# led_3.net
KiCad netlist of a schematic drawn in EAGLE
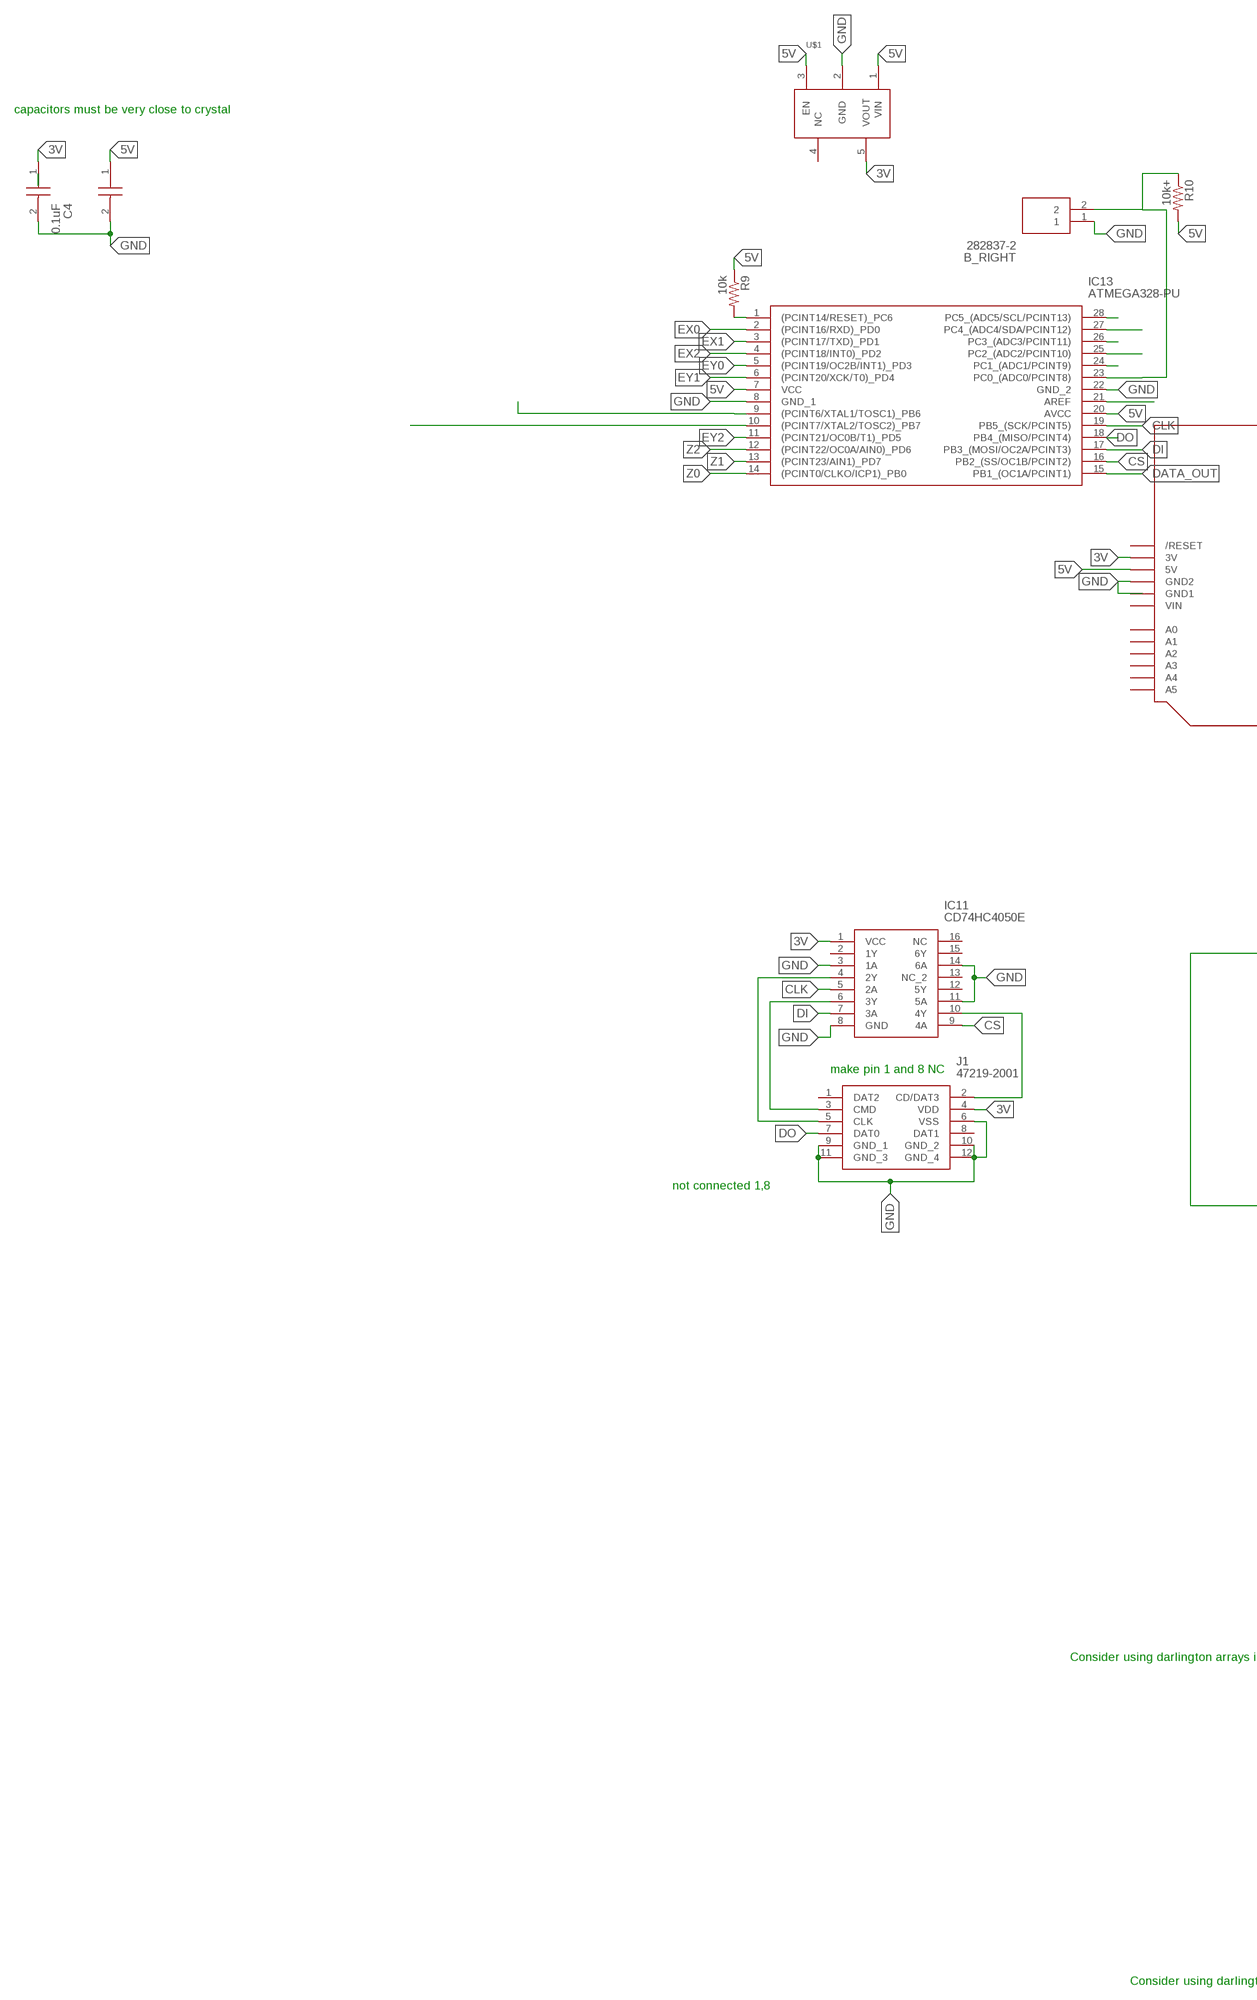
[diagram p0: schematic, sheet 1, part 1 of 2]
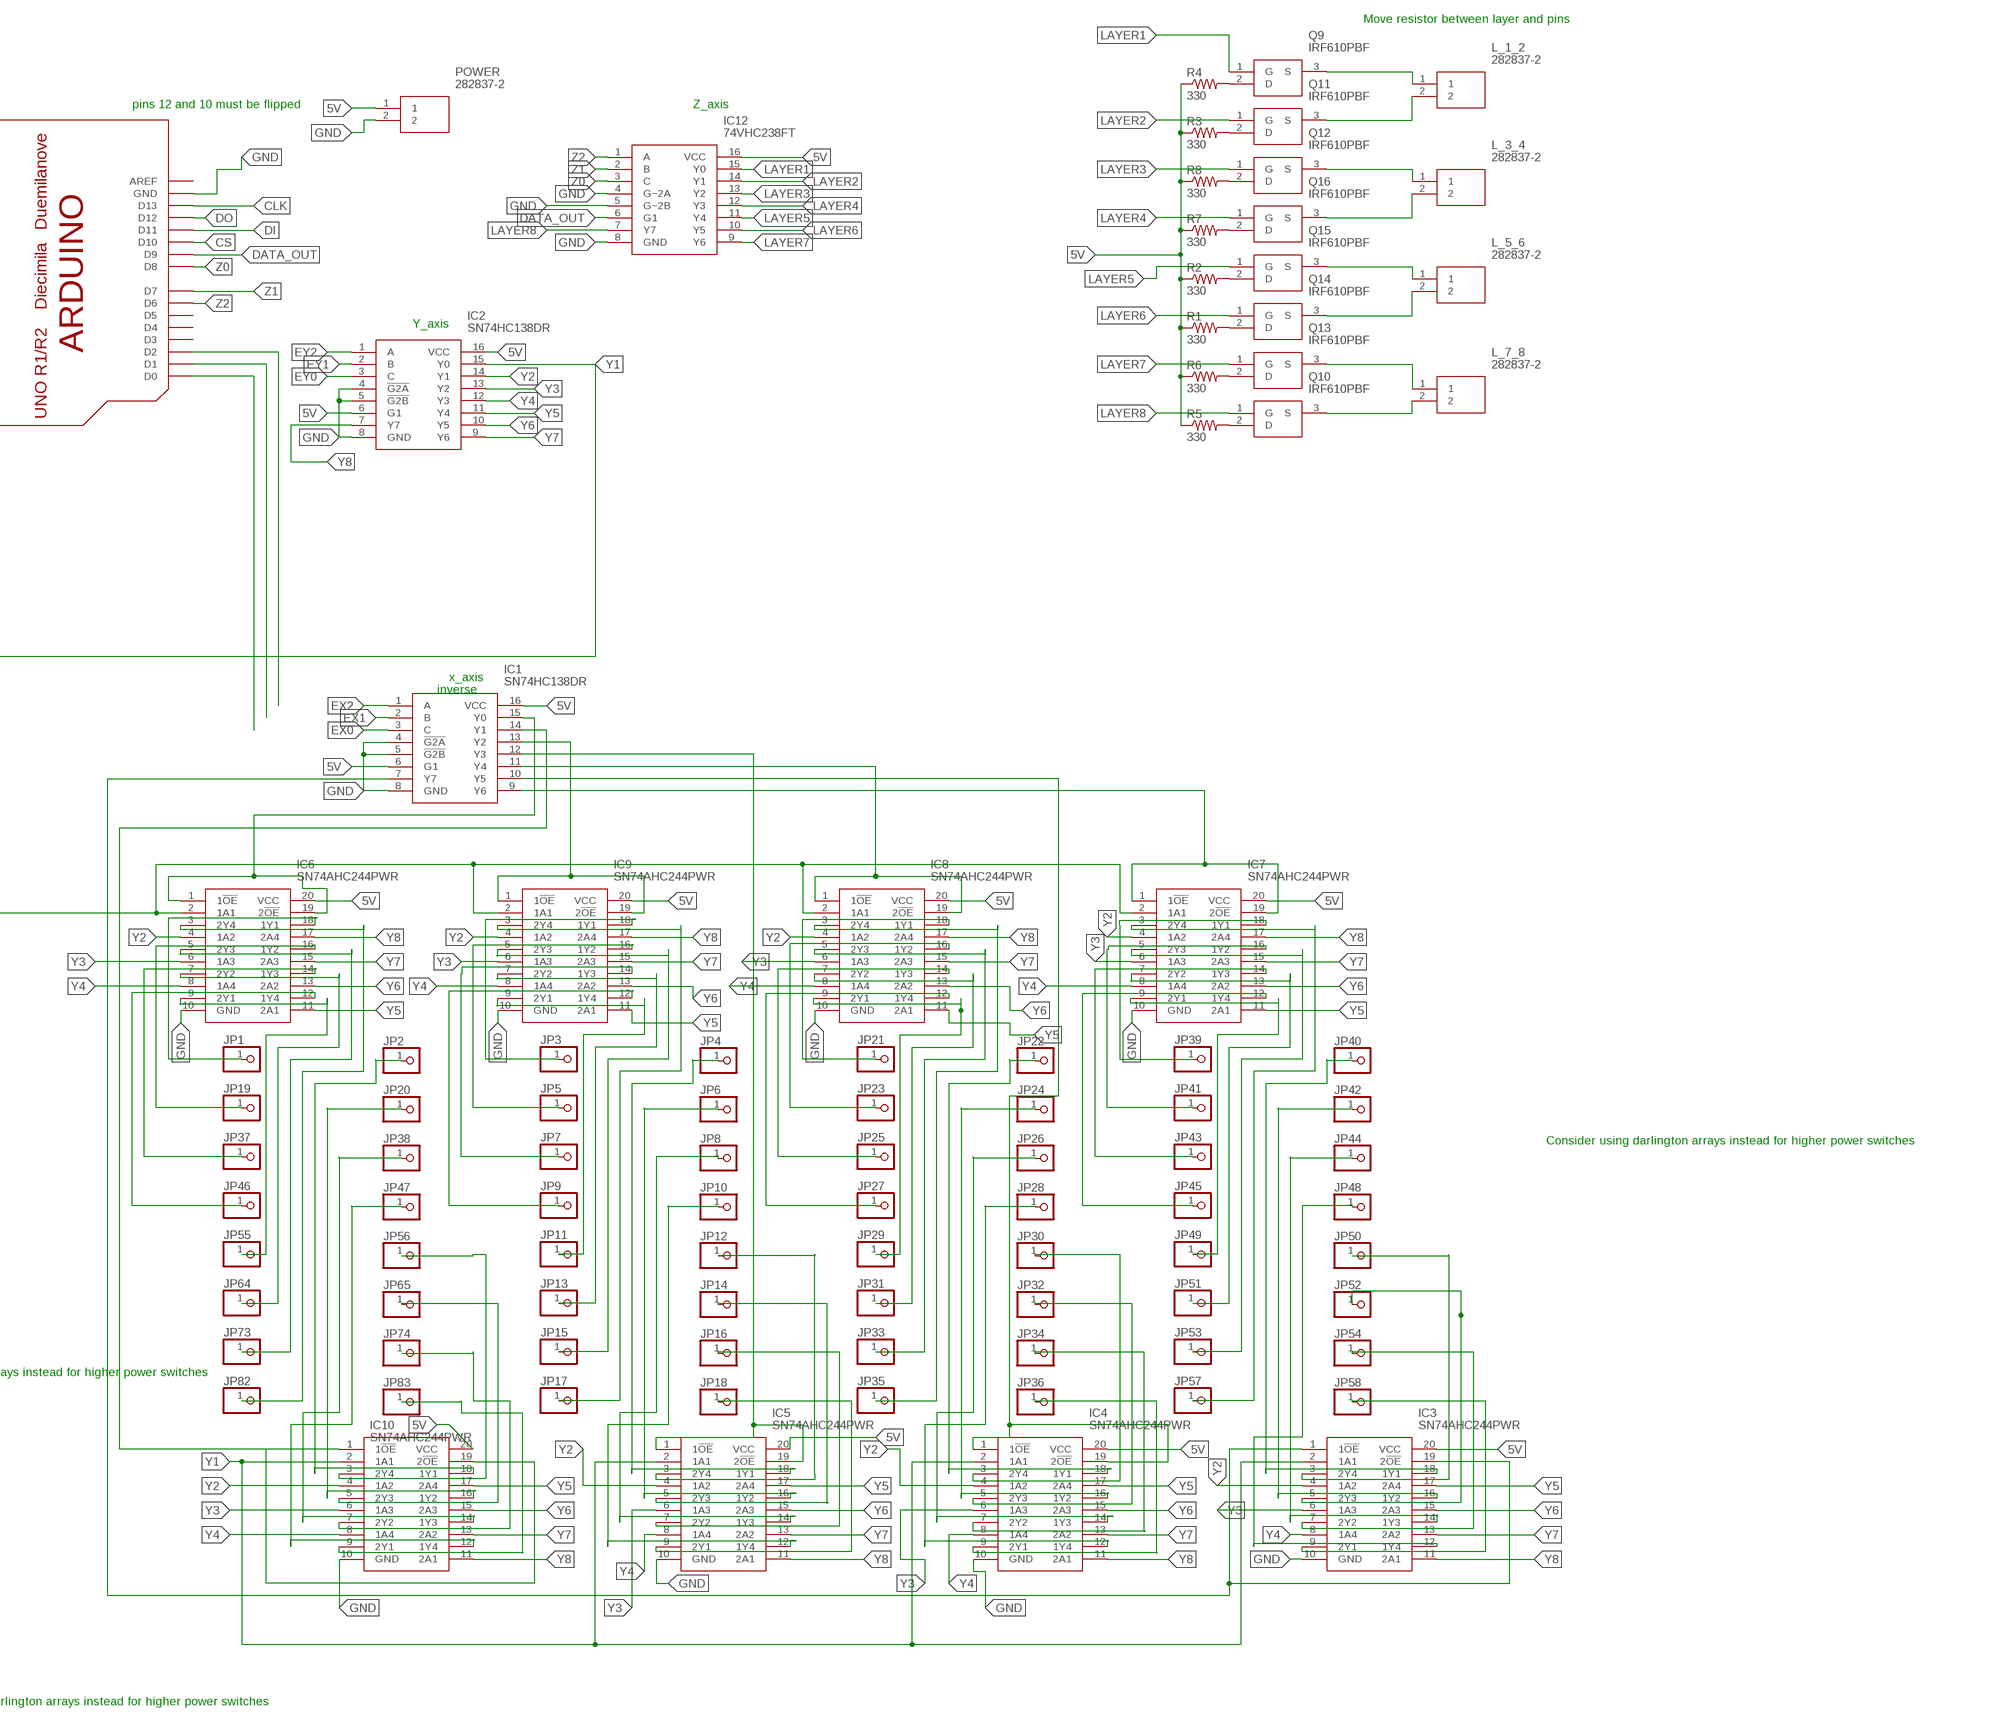
[diagram p1: schematic, sheet 1, part 2 of 2]

(export (version "E")
  (design (tool "Eeschema 10.0.6"))
  (components
    (comp (ref "B_RIGHT")
      (value "282837-2")
      (footprint "eagle-import:SHDR2W100P0X508_1X2_1016X820X1")
      (fields (field (name "MOUSER_PART_NUMBER") "571-2828372"))
      (libsource (lib "eagle-import") (part "282837-2"))
    )
    (comp (ref "C4")
      (value "0.1uF")
      (footprint "eagle-import:CAPC2012X88N")
      (fields
        (field (name "MANUFACTURER_PART_NUMBER") "C0805C224K3RACTU")
        (field (name "MOUSER_PART_NUMBER") "80-C0805C224K3R")
      )
      (libsource (lib "eagle-import") (part "C0805C224K3RACTU"))
    )
    (comp (ref "C5")
      (value "0.1uF")
      (footprint "eagle-import:CAPC2012X88N")
      (fields
        (field (name "MANUFACTURER_PART_NUMBER") "C0805C224K3RACTU")
        (field (name "MOUSER_PART_NUMBER") "80-C0805C224K3R")
      )
      (libsource (lib "eagle-import") (part "C0805C224K3RACTU"))
    )
    (comp (ref "IC1")
      (value "SN74HC138DR")
      (footprint "eagle-import:SOIC127P600X175-16N")
      (fields (field (name "MOUSER_PART_NUMBER") "595-SN74HC138DR"))
      (libsource (lib "eagle-import") (part "SN74HC138DR"))
    )
    (comp (ref "IC2")
      (value "SN74HC138DR")
      (footprint "eagle-import:SOIC127P600X175-16N")
      (fields (field (name "MOUSER_PART_NUMBER") "595-SN74HC138DR"))
      (libsource (lib "eagle-import") (part "SN74HC138DR"))
    )
    (comp (ref "IC3")
      (value "SN74AHC244PWR")
      (footprint "eagle-import:SOP65P640X120-20N")
      (fields (field (name "MOUSER_PART_NUMBER") "595-SN74AHC244PWR"))
      (libsource (lib "eagle-import") (part "SN74AHC244PWR"))
    )
    (comp (ref "IC4")
      (value "SN74AHC244PWR")
      (footprint "eagle-import:SOP65P640X120-20N")
      (fields (field (name "MOUSER_PART_NUMBER") "595-SN74AHC244PWR"))
      (libsource (lib "eagle-import") (part "SN74AHC244PWR"))
    )
    (comp (ref "IC5")
      (value "SN74AHC244PWR")
      (footprint "eagle-import:SOP65P640X120-20N")
      (fields (field (name "MOUSER_PART_NUMBER") "595-SN74AHC244PWR"))
      (libsource (lib "eagle-import") (part "SN74AHC244PWR"))
    )
    (comp (ref "IC6")
      (value "SN74AHC244PWR")
      (footprint "eagle-import:SOP65P640X120-20N")
      (fields (field (name "MOUSER_PART_NUMBER") "595-SN74AHC244PWR"))
      (libsource (lib "eagle-import") (part "SN74AHC244PWR"))
    )
    (comp (ref "IC7")
      (value "SN74AHC244PWR")
      (footprint "eagle-import:SOP65P640X120-20N")
      (fields (field (name "MOUSER_PART_NUMBER") "595-SN74AHC244PWR"))
      (libsource (lib "eagle-import") (part "SN74AHC244PWR"))
    )
    (comp (ref "IC8")
      (value "SN74AHC244PWR")
      (footprint "eagle-import:SOP65P640X120-20N")
      (fields (field (name "MOUSER_PART_NUMBER") "595-SN74AHC244PWR"))
      (libsource (lib "eagle-import") (part "SN74AHC244PWR"))
    )
    (comp (ref "IC9")
      (value "SN74AHC244PWR")
      (footprint "eagle-import:SOP65P640X120-20N")
      (fields (field (name "MOUSER_PART_NUMBER") "595-SN74AHC244PWR"))
      (libsource (lib "eagle-import") (part "SN74AHC244PWR"))
    )
    (comp (ref "IC10")
      (value "SN74AHC244PWR")
      (footprint "eagle-import:SOP65P640X120-20N")
      (fields (field (name "MOUSER_PART_NUMBER") "595-SN74AHC244PWR"))
      (libsource (lib "eagle-import") (part "SN74AHC244PWR"))
    )
    (comp (ref "IC11")
      (value "CD74HC4050E")
      (footprint "eagle-import:DIP254P762X508-16")
      (fields (field (name "MOUSER_PART_NUMBER") "595-CD74HC4050E"))
      (libsource (lib "eagle-import") (part "CD74HC4050E"))
    )
    (comp (ref "IC12")
      (value "74VHC238FT")
      (footprint "eagle-import:SOP65P640X120-16N")
      (libsource (lib "eagle-import") (part "74VHC238FT"))
    )
    (comp (ref "IC13")
      (value "ATMEGA328-PU")
      (footprint "eagle-import:DIP1016W53P254L3468H457Q28N")
      (fields (field (name "MOUSER_PART_NUMBER") "556-ATMEGA328-PU"))
      (libsource (lib "eagle-import") (part "ATMEGA328-PU"))
    )
    (comp (ref "J1")
      (value "47219-2001")
      (footprint "eagle-import:472192001")
      (fields (field (name "MOUSER_PART_NUMBER") "538-47219-2001"))
      (libsource (lib "eagle-import") (part "47219-2001"))
    )
    (comp (ref "JP1")
      (value "PINHD-1X1")
      (footprint "eagle-import:1X01")
      (libsource (lib "eagle-import") (part "PINHD-1X1"))
    )
    (comp (ref "JP2")
      (value "PINHD-1X1")
      (footprint "eagle-import:1X01")
      (libsource (lib "eagle-import") (part "PINHD-1X1"))
    )
    (comp (ref "JP3")
      (value "PINHD-1X1")
      (footprint "eagle-import:1X01")
      (libsource (lib "eagle-import") (part "PINHD-1X1"))
    )
    (comp (ref "JP4")
      (value "PINHD-1X1")
      (footprint "eagle-import:1X01")
      (libsource (lib "eagle-import") (part "PINHD-1X1"))
    )
    (comp (ref "JP5")
      (value "PINHD-1X1")
      (footprint "eagle-import:1X01")
      (libsource (lib "eagle-import") (part "PINHD-1X1"))
    )
    (comp (ref "JP6")
      (value "PINHD-1X1")
      (footprint "eagle-import:1X01")
      (libsource (lib "eagle-import") (part "PINHD-1X1"))
    )
    (comp (ref "JP7")
      (value "PINHD-1X1")
      (footprint "eagle-import:1X01")
      (libsource (lib "eagle-import") (part "PINHD-1X1"))
    )
    (comp (ref "JP8")
      (value "PINHD-1X1")
      (footprint "eagle-import:1X01")
      (libsource (lib "eagle-import") (part "PINHD-1X1"))
    )
    (comp (ref "JP9")
      (value "PINHD-1X1")
      (footprint "eagle-import:1X01")
      (libsource (lib "eagle-import") (part "PINHD-1X1"))
    )
    (comp (ref "JP10")
      (value "PINHD-1X1")
      (footprint "eagle-import:1X01")
      (libsource (lib "eagle-import") (part "PINHD-1X1"))
    )
    (comp (ref "JP11")
      (value "PINHD-1X1")
      (footprint "eagle-import:1X01")
      (libsource (lib "eagle-import") (part "PINHD-1X1"))
    )
    (comp (ref "JP12")
      (value "PINHD-1X1")
      (footprint "eagle-import:1X01")
      (libsource (lib "eagle-import") (part "PINHD-1X1"))
    )
    (comp (ref "JP13")
      (value "PINHD-1X1")
      (footprint "eagle-import:1X01")
      (libsource (lib "eagle-import") (part "PINHD-1X1"))
    )
    (comp (ref "JP14")
      (value "PINHD-1X1")
      (footprint "eagle-import:1X01")
      (libsource (lib "eagle-import") (part "PINHD-1X1"))
    )
    (comp (ref "JP15")
      (value "PINHD-1X1")
      (footprint "eagle-import:1X01")
      (libsource (lib "eagle-import") (part "PINHD-1X1"))
    )
    (comp (ref "JP16")
      (value "PINHD-1X1")
      (footprint "eagle-import:1X01")
      (libsource (lib "eagle-import") (part "PINHD-1X1"))
    )
    (comp (ref "JP17")
      (value "PINHD-1X1")
      (footprint "eagle-import:1X01")
      (libsource (lib "eagle-import") (part "PINHD-1X1"))
    )
    (comp (ref "JP18")
      (value "PINHD-1X1")
      (footprint "eagle-import:1X01")
      (libsource (lib "eagle-import") (part "PINHD-1X1"))
    )
    (comp (ref "JP19")
      (value "PINHD-1X1")
      (footprint "eagle-import:1X01")
      (libsource (lib "eagle-import") (part "PINHD-1X1"))
    )
    (comp (ref "JP20")
      (value "PINHD-1X1")
      (footprint "eagle-import:1X01")
      (libsource (lib "eagle-import") (part "PINHD-1X1"))
    )
    (comp (ref "JP21")
      (value "PINHD-1X1")
      (footprint "eagle-import:1X01")
      (libsource (lib "eagle-import") (part "PINHD-1X1"))
    )
    (comp (ref "JP22")
      (value "PINHD-1X1")
      (footprint "eagle-import:1X01")
      (libsource (lib "eagle-import") (part "PINHD-1X1"))
    )
    (comp (ref "JP23")
      (value "PINHD-1X1")
      (footprint "eagle-import:1X01")
      (libsource (lib "eagle-import") (part "PINHD-1X1"))
    )
    (comp (ref "JP24")
      (value "PINHD-1X1")
      (footprint "eagle-import:1X01")
      (libsource (lib "eagle-import") (part "PINHD-1X1"))
    )
    (comp (ref "JP25")
      (value "PINHD-1X1")
      (footprint "eagle-import:1X01")
      (libsource (lib "eagle-import") (part "PINHD-1X1"))
    )
    (comp (ref "JP26")
      (value "PINHD-1X1")
      (footprint "eagle-import:1X01")
      (libsource (lib "eagle-import") (part "PINHD-1X1"))
    )
    (comp (ref "JP27")
      (value "PINHD-1X1")
      (footprint "eagle-import:1X01")
      (libsource (lib "eagle-import") (part "PINHD-1X1"))
    )
    (comp (ref "JP28")
      (value "PINHD-1X1")
      (footprint "eagle-import:1X01")
      (libsource (lib "eagle-import") (part "PINHD-1X1"))
    )
    (comp (ref "JP29")
      (value "PINHD-1X1")
      (footprint "eagle-import:1X01")
      (libsource (lib "eagle-import") (part "PINHD-1X1"))
    )
    (comp (ref "JP30")
      (value "PINHD-1X1")
      (footprint "eagle-import:1X01")
      (libsource (lib "eagle-import") (part "PINHD-1X1"))
    )
    (comp (ref "JP31")
      (value "PINHD-1X1")
      (footprint "eagle-import:1X01")
      (libsource (lib "eagle-import") (part "PINHD-1X1"))
    )
    (comp (ref "JP32")
      (value "PINHD-1X1")
      (footprint "eagle-import:1X01")
      (libsource (lib "eagle-import") (part "PINHD-1X1"))
    )
    (comp (ref "JP33")
      (value "PINHD-1X1")
      (footprint "eagle-import:1X01")
      (libsource (lib "eagle-import") (part "PINHD-1X1"))
    )
    (comp (ref "JP34")
      (value "PINHD-1X1")
      (footprint "eagle-import:1X01")
      (libsource (lib "eagle-import") (part "PINHD-1X1"))
    )
    (comp (ref "JP35")
      (value "PINHD-1X1")
      (footprint "eagle-import:1X01")
      (libsource (lib "eagle-import") (part "PINHD-1X1"))
    )
    (comp (ref "JP36")
      (value "PINHD-1X1")
      (footprint "eagle-import:1X01")
      (libsource (lib "eagle-import") (part "PINHD-1X1"))
    )
    (comp (ref "JP37")
      (value "PINHD-1X1")
      (footprint "eagle-import:1X01")
      (libsource (lib "eagle-import") (part "PINHD-1X1"))
    )
    (comp (ref "JP38")
      (value "PINHD-1X1")
      (footprint "eagle-import:1X01")
      (libsource (lib "eagle-import") (part "PINHD-1X1"))
    )
    (comp (ref "JP39")
      (value "PINHD-1X1")
      (footprint "eagle-import:1X01")
      (libsource (lib "eagle-import") (part "PINHD-1X1"))
    )
    (comp (ref "JP40")
      (value "PINHD-1X1")
      (footprint "eagle-import:1X01")
      (libsource (lib "eagle-import") (part "PINHD-1X1"))
    )
    (comp (ref "JP41")
      (value "PINHD-1X1")
      (footprint "eagle-import:1X01")
      (libsource (lib "eagle-import") (part "PINHD-1X1"))
    )
    (comp (ref "JP42")
      (value "PINHD-1X1")
      (footprint "eagle-import:1X01")
      (libsource (lib "eagle-import") (part "PINHD-1X1"))
    )
    (comp (ref "JP43")
      (value "PINHD-1X1")
      (footprint "eagle-import:1X01")
      (libsource (lib "eagle-import") (part "PINHD-1X1"))
    )
    (comp (ref "JP44")
      (value "PINHD-1X1")
      (footprint "eagle-import:1X01")
      (libsource (lib "eagle-import") (part "PINHD-1X1"))
    )
    (comp (ref "JP45")
      (value "PINHD-1X1")
      (footprint "eagle-import:1X01")
      (libsource (lib "eagle-import") (part "PINHD-1X1"))
    )
    (comp (ref "JP46")
      (value "PINHD-1X1")
      (footprint "eagle-import:1X01")
      (libsource (lib "eagle-import") (part "PINHD-1X1"))
    )
    (comp (ref "JP47")
      (value "PINHD-1X1")
      (footprint "eagle-import:1X01")
      (libsource (lib "eagle-import") (part "PINHD-1X1"))
    )
    (comp (ref "JP48")
      (value "PINHD-1X1")
      (footprint "eagle-import:1X01")
      (libsource (lib "eagle-import") (part "PINHD-1X1"))
    )
    (comp (ref "JP49")
      (value "PINHD-1X1")
      (footprint "eagle-import:1X01")
      (libsource (lib "eagle-import") (part "PINHD-1X1"))
    )
    (comp (ref "JP50")
      (value "PINHD-1X1")
      (footprint "eagle-import:1X01")
      (libsource (lib "eagle-import") (part "PINHD-1X1"))
    )
    (comp (ref "JP51")
      (value "PINHD-1X1")
      (footprint "eagle-import:1X01")
      (libsource (lib "eagle-import") (part "PINHD-1X1"))
    )
    (comp (ref "JP52")
      (value "PINHD-1X1")
      (footprint "eagle-import:1X01")
      (libsource (lib "eagle-import") (part "PINHD-1X1"))
    )
    (comp (ref "JP53")
      (value "PINHD-1X1")
      (footprint "eagle-import:1X01")
      (libsource (lib "eagle-import") (part "PINHD-1X1"))
    )
    (comp (ref "JP54")
      (value "PINHD-1X1")
      (footprint "eagle-import:1X01")
      (libsource (lib "eagle-import") (part "PINHD-1X1"))
    )
    (comp (ref "JP55")
      (value "PINHD-1X1")
      (footprint "eagle-import:1X01")
      (libsource (lib "eagle-import") (part "PINHD-1X1"))
    )
    (comp (ref "JP56")
      (value "PINHD-1X1")
      (footprint "eagle-import:1X01")
      (libsource (lib "eagle-import") (part "PINHD-1X1"))
    )
    (comp (ref "JP57")
      (value "PINHD-1X1")
      (footprint "eagle-import:1X01")
      (libsource (lib "eagle-import") (part "PINHD-1X1"))
    )
    (comp (ref "JP58")
      (value "PINHD-1X1")
      (footprint "eagle-import:1X01")
      (libsource (lib "eagle-import") (part "PINHD-1X1"))
    )
    (comp (ref "JP64")
      (value "PINHD-1X1")
      (footprint "eagle-import:1X01")
      (libsource (lib "eagle-import") (part "PINHD-1X1"))
    )
    (comp (ref "JP65")
      (value "PINHD-1X1")
      (footprint "eagle-import:1X01")
      (libsource (lib "eagle-import") (part "PINHD-1X1"))
    )
    (comp (ref "JP73")
      (value "PINHD-1X1")
      (footprint "eagle-import:1X01")
      (libsource (lib "eagle-import") (part "PINHD-1X1"))
    )
    (comp (ref "JP74")
      (value "PINHD-1X1")
      (footprint "eagle-import:1X01")
      (libsource (lib "eagle-import") (part "PINHD-1X1"))
    )
    (comp (ref "JP82")
      (value "PINHD-1X1")
      (footprint "eagle-import:1X01")
      (libsource (lib "eagle-import") (part "PINHD-1X1"))
    )
    (comp (ref "JP83")
      (value "PINHD-1X1")
      (footprint "eagle-import:1X01")
      (libsource (lib "eagle-import") (part "PINHD-1X1"))
    )
    (comp (ref "L_1_2")
      (value "282837-2")
      (footprint "eagle-import:SHDR2W100P0X508_1X2_1016X820X1")
      (fields (field (name "MOUSER_PART_NUMBER") "571-2828372"))
      (libsource (lib "eagle-import") (part "282837-2"))
    )
    (comp (ref "L_3_4")
      (value "282837-2")
      (footprint "eagle-import:SHDR2W100P0X508_1X2_1016X820X1")
      (fields (field (name "MOUSER_PART_NUMBER") "571-2828372"))
      (libsource (lib "eagle-import") (part "282837-2"))
    )
    (comp (ref "L_5_6")
      (value "282837-2")
      (footprint "eagle-import:SHDR2W100P0X508_1X2_1016X820X1")
      (fields (field (name "MOUSER_PART_NUMBER") "571-2828372"))
      (libsource (lib "eagle-import") (part "282837-2"))
    )
    (comp (ref "L_7_8")
      (value "282837-2")
      (footprint "eagle-import:SHDR2W100P0X508_1X2_1016X820X1")
      (fields (field (name "MOUSER_PART_NUMBER") "571-2828372"))
      (libsource (lib "eagle-import") (part "282837-2"))
    )
    (comp (ref "POWER")
      (value "282837-2")
      (footprint "eagle-import:SHDR2W100P0X508_1X2_1016X820X1")
      (fields (field (name "MOUSER_PART_NUMBER") "571-2828372"))
      (libsource (lib "eagle-import") (part "282837-2"))
    )
    (comp (ref "Q9")
      (value "IRF610PBF")
      (footprint "eagle-import:TO254P465X1024X2050-3P")
      (fields (field (name "MOUSER_PART_NUMBER") "844-IRF610PBF"))
      (libsource (lib "eagle-import") (part "IRF610PBF"))
    )
    (comp (ref "Q10")
      (value "IRF610PBF")
      (footprint "eagle-import:TO254P465X1024X2050-3P")
      (fields (field (name "MOUSER_PART_NUMBER") "844-IRF610PBF"))
      (libsource (lib "eagle-import") (part "IRF610PBF"))
    )
    (comp (ref "Q11")
      (value "IRF610PBF")
      (footprint "eagle-import:TO254P465X1024X2050-3P")
      (fields (field (name "MOUSER_PART_NUMBER") "844-IRF610PBF"))
      (libsource (lib "eagle-import") (part "IRF610PBF"))
    )
    (comp (ref "Q12")
      (value "IRF610PBF")
      (footprint "eagle-import:TO254P465X1024X2050-3P")
      (fields (field (name "MOUSER_PART_NUMBER") "844-IRF610PBF"))
      (libsource (lib "eagle-import") (part "IRF610PBF"))
    )
    (comp (ref "Q13")
      (value "IRF610PBF")
      (footprint "eagle-import:TO254P465X1024X2050-3P")
      (fields (field (name "MOUSER_PART_NUMBER") "844-IRF610PBF"))
      (libsource (lib "eagle-import") (part "IRF610PBF"))
    )
    (comp (ref "Q14")
      (value "IRF610PBF")
      (footprint "eagle-import:TO254P465X1024X2050-3P")
      (fields (field (name "MOUSER_PART_NUMBER") "844-IRF610PBF"))
      (libsource (lib "eagle-import") (part "IRF610PBF"))
    )
    (comp (ref "Q15")
      (value "IRF610PBF")
      (footprint "eagle-import:TO254P465X1024X2050-3P")
      (fields (field (name "MOUSER_PART_NUMBER") "844-IRF610PBF"))
      (libsource (lib "eagle-import") (part "IRF610PBF"))
    )
    (comp (ref "Q16")
      (value "IRF610PBF")
      (footprint "eagle-import:TO254P465X1024X2050-3P")
      (fields (field (name "MOUSER_PART_NUMBER") "844-IRF610PBF"))
      (libsource (lib "eagle-import") (part "IRF610PBF"))
    )
    (comp (ref "R1")
      (value "330")
      (footprint "eagle-import:0207_12")
      (libsource (lib "eagle-import") (part "R-US_0207/12"))
    )
    (comp (ref "R2")
      (value "330")
      (footprint "eagle-import:0207_12")
      (libsource (lib "eagle-import") (part "R-US_0207/12"))
    )
    (comp (ref "R3")
      (value "330")
      (footprint "eagle-import:0207_12")
      (libsource (lib "eagle-import") (part "R-US_0207/12"))
    )
    (comp (ref "R4")
      (value "330")
      (footprint "eagle-import:0207_12")
      (libsource (lib "eagle-import") (part "R-US_0207/12"))
    )
    (comp (ref "R5")
      (value "330")
      (footprint "eagle-import:0207_12")
      (libsource (lib "eagle-import") (part "R-US_0207/12"))
    )
    (comp (ref "R6")
      (value "330")
      (footprint "eagle-import:0207_12")
      (libsource (lib "eagle-import") (part "R-US_0207/12"))
    )
    (comp (ref "R7")
      (value "330")
      (footprint "eagle-import:0207_12")
      (libsource (lib "eagle-import") (part "R-US_0207/12"))
    )
    (comp (ref "R8")
      (value "330")
      (footprint "eagle-import:0207_12")
      (libsource (lib "eagle-import") (part "R-US_0207/12"))
    )
    (comp (ref "R9")
      (value "10k")
      (footprint "eagle-import:M0805")
      (libsource (lib "eagle-import") (part "R-US_M0805"))
    )
    (comp (ref "R10")
      (value "10k+")
      (footprint "eagle-import:M0805")
      (libsource (lib "eagle-import") (part "R-US_M0805"))
    )
    (comp (ref "U$1")
      (value "MIC5501")
      (footprint "eagle-import:SOT23(M5)")
      (libsource (lib "eagle-import") (part "MIC5501"))
    )
    (comp (ref "U$2")
      (value "ARDUINO-NOHOLE")
      (footprint "eagle-import:ARDUINO-NOHOLE")
      (libsource (lib "eagle-import") (part "ARDUINO-NOHOLE"))
    )
  )
  (nets
    (net (code "1") (name "/VIN") (class "Default")
      (node (ref "U$2") (pin "VIN") (pinfunction "VIN_VIN") (pintype "power_in"))
    )
    (net (code "2") (name "3V") (class "Default")
      (node (ref "C4") (pin "1") (pinfunction "1_1") (pintype "bidirectional"))
      (node (ref "IC11") (pin "1") (pinfunction "VCC_1") (pintype "bidirectional"))
      (node (ref "J1") (pin "4") (pinfunction "VDD_4") (pintype "bidirectional"))
      (node (ref "U$1") (pin "5") (pinfunction "VOUT_5") (pintype "bidirectional"))
      (node (ref "U$2") (pin "3V") (pinfunction "3V_3V") (pintype "power_in"))
    )
    (net (code "3") (name "5V") (class "Default")
      (node (ref "C5") (pin "1") (pinfunction "1_1") (pintype "bidirectional"))
      (node (ref "IC1") (pin "16") (pinfunction "VCC_16") (pintype "power_in"))
      (node (ref "IC1") (pin "6") (pinfunction "G1_6") (pintype "bidirectional"))
      (node (ref "IC10") (pin "20") (pinfunction "VCC_20") (pintype "bidirectional"))
      (node (ref "IC12") (pin "16") (pinfunction "VCC_16") (pintype "power_in"))
      (node (ref "IC13") (pin "20") (pinfunction "AVCC_20") (pintype "power_in"))
      (node (ref "IC13") (pin "7") (pinfunction "VCC_7") (pintype "power_in"))
      (node (ref "IC2") (pin "16") (pinfunction "VCC_16") (pintype "power_in"))
      (node (ref "IC2") (pin "6") (pinfunction "G1_6") (pintype "bidirectional"))
      (node (ref "IC3") (pin "20") (pinfunction "VCC_20") (pintype "bidirectional"))
      (node (ref "IC4") (pin "20") (pinfunction "VCC_20") (pintype "bidirectional"))
      (node (ref "IC5") (pin "20") (pinfunction "VCC_20") (pintype "bidirectional"))
      (node (ref "IC6") (pin "20") (pinfunction "VCC_20") (pintype "bidirectional"))
      (node (ref "IC7") (pin "20") (pinfunction "VCC_20") (pintype "bidirectional"))
      (node (ref "IC8") (pin "20") (pinfunction "VCC_20") (pintype "bidirectional"))
      (node (ref "IC9") (pin "20") (pinfunction "VCC_20") (pintype "bidirectional"))
      (node (ref "POWER") (pin "1") (pinfunction "1_1") (pintype "bidirectional"))
      (node (ref "R1") (pin "1") (pinfunction "1_1") (pintype "passive"))
      (node (ref "R10") (pin "2") (pinfunction "2_2") (pintype "passive"))
      (node (ref "R2") (pin "1") (pinfunction "1_1") (pintype "passive"))
      (node (ref "R3") (pin "1") (pinfunction "1_1") (pintype "passive"))
      (node (ref "R4") (pin "1") (pinfunction "1_1") (pintype "passive"))
      (node (ref "R5") (pin "1") (pinfunction "1_1") (pintype "passive"))
      (node (ref "R6") (pin "1") (pinfunction "1_1") (pintype "passive"))
      (node (ref "R7") (pin "1") (pinfunction "1_1") (pintype "passive"))
      (node (ref "R8") (pin "1") (pinfunction "1_1") (pintype "passive"))
      (node (ref "R9") (pin "1") (pinfunction "1_1") (pintype "passive"))
      (node (ref "U$1") (pin "1") (pinfunction "VIN_1") (pintype "bidirectional"))
      (node (ref "U$1") (pin "3") (pinfunction "EN_3") (pintype "bidirectional"))
      (node (ref "U$2") (pin "5V") (pinfunction "5V_5V") (pintype "power_in"))
    )
    (net (code "4") (name "CLK") (class "Default")
      (node (ref "IC11") (pin "5") (pinfunction "2A_5") (pintype "bidirectional"))
      (node (ref "IC13") (pin "19") (pinfunction "PB5_(SCK/PCINT5)_19") (pintype "bidirectional"))
      (node (ref "U$2") (pin "D13") (pinfunction "D13_D13") (pintype "bidirectional"))
    )
    (net (code "5") (name "CS") (class "Default")
      (node (ref "IC11") (pin "9") (pinfunction "4A_9") (pintype "bidirectional"))
      (node (ref "IC13") (pin "16") (pinfunction "PB2_(SS/OC1B/PCINT2)_16") (pintype "bidirectional"))
      (node (ref "U$2") (pin "D10") (pinfunction "D10_D10") (pintype "bidirectional"))
    )
    (net (code "6") (name "DATA_OUT") (class "Default")
      (node (ref "IC12") (pin "6") (pinfunction "G1_6") (pintype "input"))
      (node (ref "IC13") (pin "15") (pinfunction "PB1_(OC1A/PCINT1)_15") (pintype "bidirectional"))
      (node (ref "U$2") (pin "D9") (pinfunction "D9_D9") (pintype "bidirectional"))
    )
    (net (code "7") (name "DI") (class "Default")
      (node (ref "IC11") (pin "7") (pinfunction "3A_7") (pintype "bidirectional"))
      (node (ref "IC13") (pin "17") (pinfunction "PB3_(MOSI/OC2A/PCINT3)_17") (pintype "bidirectional"))
      (node (ref "U$2") (pin "D11") (pinfunction "D11_D11") (pintype "bidirectional"))
    )
    (net (code "8") (name "DO") (class "Default")
      (node (ref "IC13") (pin "18") (pinfunction "PB4_(MISO/PCINT4)_18") (pintype "bidirectional"))
      (node (ref "J1") (pin "7") (pinfunction "DAT0_7") (pintype "bidirectional"))
      (node (ref "U$2") (pin "D12") (pinfunction "D12_D12") (pintype "bidirectional"))
    )
    (net (code "9") (name "EX0") (class "Default")
      (node (ref "IC1") (pin "3") (pinfunction "C_3") (pintype "bidirectional"))
      (node (ref "IC13") (pin "2") (pinfunction "(PCINT16/RXD)_PD0_2") (pintype "input"))
    )
    (net (code "10") (name "EX1") (class "Default")
      (node (ref "IC1") (pin "2") (pinfunction "B_2") (pintype "bidirectional"))
      (node (ref "IC13") (pin "3") (pinfunction "(PCINT17/TXD)_PD1_3") (pintype "output"))
    )
    (net (code "11") (name "EX2") (class "Default")
      (node (ref "IC1") (pin "1") (pinfunction "A_1") (pintype "bidirectional"))
      (node (ref "IC13") (pin "4") (pinfunction "(PCINT18/INT0)_PD2_4") (pintype "bidirectional"))
    )
    (net (code "12") (name "EY0") (class "Default")
      (node (ref "IC13") (pin "5") (pinfunction "(PCINT19/OC2B/INT1)_PD3_5") (pintype "bidirectional"))
      (node (ref "IC2") (pin "3") (pinfunction "C_3") (pintype "bidirectional"))
    )
    (net (code "13") (name "EY1") (class "Default")
      (node (ref "IC13") (pin "6") (pinfunction "(PCINT20/XCK/T0)_PD4_6") (pintype "bidirectional"))
      (node (ref "IC2") (pin "2") (pinfunction "B_2") (pintype "bidirectional"))
    )
    (net (code "14") (name "EY2") (class "Default")
      (node (ref "IC13") (pin "11") (pinfunction "(PCINT21/OC0B/T1)_PD5_11") (pintype "bidirectional"))
      (node (ref "IC2") (pin "1") (pinfunction "A_1") (pintype "bidirectional"))
    )
    (net (code "15") (name "GND") (class "Default")
      (node (ref "B_RIGHT") (pin "1") (pinfunction "1_1") (pintype "bidirectional"))
      (node (ref "C4") (pin "2") (pinfunction "2_2") (pintype "bidirectional"))
      (node (ref "C5") (pin "2") (pinfunction "2_2") (pintype "bidirectional"))
      (node (ref "IC1") (pin "4") (pinfunction "~{G2A}_4") (pintype "bidirectional"))
      (node (ref "IC1") (pin "5") (pinfunction "~{G2B}_5") (pintype "bidirectional"))
      (node (ref "IC1") (pin "8") (pinfunction "GND_8") (pintype "power_in"))
      (node (ref "IC10") (pin "10") (pinfunction "GND_10") (pintype "bidirectional"))
      (node (ref "IC11") (pin "11") (pinfunction "5A_11") (pintype "bidirectional"))
      (node (ref "IC11") (pin "14") (pinfunction "6A_14") (pintype "bidirectional"))
      (node (ref "IC11") (pin "3") (pinfunction "1A_3") (pintype "bidirectional"))
      (node (ref "IC11") (pin "8") (pinfunction "GND_8") (pintype "bidirectional"))
      (node (ref "IC12") (pin "4") (pinfunction "G~{2A}_4") (pintype "input"))
      (node (ref "IC12") (pin "5") (pinfunction "G~{2B}_5") (pintype "input"))
      (node (ref "IC12") (pin "8") (pinfunction "GND_8") (pintype "power_in"))
      (node (ref "IC13") (pin "22") (pinfunction "GND_2_22") (pintype "power_in"))
      (node (ref "IC13") (pin "8") (pinfunction "GND_1_8") (pintype "power_in"))
      (node (ref "IC2") (pin "4") (pinfunction "~{G2A}_4") (pintype "bidirectional"))
      (node (ref "IC2") (pin "5") (pinfunction "~{G2B}_5") (pintype "bidirectional"))
      (node (ref "IC2") (pin "8") (pinfunction "GND_8") (pintype "power_in"))
      (node (ref "IC3") (pin "10") (pinfunction "GND_10") (pintype "bidirectional"))
      (node (ref "IC4") (pin "10") (pinfunction "GND_10") (pintype "bidirectional"))
      (node (ref "IC5") (pin "10") (pinfunction "GND_10") (pintype "bidirectional"))
      (node (ref "IC6") (pin "10") (pinfunction "GND_10") (pintype "bidirectional"))
      (node (ref "IC7") (pin "10") (pinfunction "GND_10") (pintype "bidirectional"))
      (node (ref "IC8") (pin "10") (pinfunction "GND_10") (pintype "bidirectional"))
      (node (ref "IC9") (pin "10") (pinfunction "GND_10") (pintype "bidirectional"))
      (node (ref "J1") (pin "10") (pinfunction "GND_2_10") (pintype "bidirectional"))
      (node (ref "J1") (pin "11") (pinfunction "GND_3_11") (pintype "bidirectional"))
      (node (ref "J1") (pin "12") (pinfunction "GND_4_12") (pintype "bidirectional"))
      (node (ref "J1") (pin "6") (pinfunction "VSS_6") (pintype "bidirectional"))
      (node (ref "J1") (pin "9") (pinfunction "GND_1_9") (pintype "bidirectional"))
      (node (ref "POWER") (pin "2") (pinfunction "2_2") (pintype "bidirectional"))
      (node (ref "U$1") (pin "2") (pinfunction "GND_2") (pintype "bidirectional"))
      (node (ref "U$2") (pin "GND") (pinfunction "GND_GND") (pintype "power_in"))
      (node (ref "U$2") (pin "GND1") (pinfunction "GND1_GND1") (pintype "power_in"))
      (node (ref "U$2") (pin "GND2") (pinfunction "GND2_GND2") (pintype "power_in"))
    )
    (net (code "16") (name "LAYER1") (class "Default")
      (node (ref "IC12") (pin "15") (pinfunction "Y0_15") (pintype "output"))
      (node (ref "Q9") (pin "1") (pinfunction "G_1") (pintype "bidirectional"))
    )
    (net (code "17") (name "LAYER2") (class "Default")
      (node (ref "IC12") (pin "14") (pinfunction "Y1_14") (pintype "output"))
      (node (ref "Q11") (pin "1") (pinfunction "G_1") (pintype "bidirectional"))
    )
    (net (code "18") (name "LAYER3") (class "Default")
      (node (ref "IC12") (pin "13") (pinfunction "Y2_13") (pintype "output"))
      (node (ref "Q12") (pin "1") (pinfunction "G_1") (pintype "bidirectional"))
    )
    (net (code "19") (name "LAYER4") (class "Default")
      (node (ref "IC12") (pin "12") (pinfunction "Y3_12") (pintype "output"))
      (node (ref "Q16") (pin "1") (pinfunction "G_1") (pintype "bidirectional"))
    )
    (net (code "20") (name "LAYER5") (class "Default")
      (node (ref "IC12") (pin "11") (pinfunction "Y4_11") (pintype "output"))
      (node (ref "Q15") (pin "1") (pinfunction "G_1") (pintype "bidirectional"))
    )
    (net (code "21") (name "LAYER6") (class "Default")
      (node (ref "IC12") (pin "10") (pinfunction "Y5_10") (pintype "output"))
      (node (ref "Q14") (pin "1") (pinfunction "G_1") (pintype "bidirectional"))
    )
    (net (code "22") (name "LAYER7") (class "Default")
      (node (ref "IC12") (pin "9") (pinfunction "Y6_9") (pintype "output"))
      (node (ref "Q13") (pin "1") (pinfunction "G_1") (pintype "bidirectional"))
    )
    (net (code "23") (name "LAYER8") (class "Default")
      (node (ref "IC12") (pin "7") (pinfunction "Y7_7") (pintype "output"))
      (node (ref "Q10") (pin "1") (pinfunction "G_1") (pintype "bidirectional"))
    )
    (net (code "24") (name "Net-(IC1-Y0)") (class "Default")
      (node (ref "IC1") (pin "15") (pinfunction "Y0_15") (pintype "bidirectional"))
      (node (ref "IC6") (pin "1") (pinfunction "1~{OE}_1") (pintype "bidirectional"))
      (node (ref "IC6") (pin "19") (pinfunction "2~{OE}_19") (pintype "bidirectional"))
    )
    (net (code "25") (name "Net-(IC1-Y1)") (class "Default")
      (node (ref "IC1") (pin "14") (pinfunction "Y1_14") (pintype "bidirectional"))
      (node (ref "IC10") (pin "1") (pinfunction "1~{OE}_1") (pintype "bidirectional"))
      (node (ref "IC10") (pin "19") (pinfunction "2~{OE}_19") (pintype "bidirectional"))
    )
    (net (code "26") (name "Net-(IC1-Y2)") (class "Default")
      (node (ref "IC1") (pin "13") (pinfunction "Y2_13") (pintype "bidirectional"))
      (node (ref "IC9") (pin "1") (pinfunction "1~{OE}_1") (pintype "bidirectional"))
      (node (ref "IC9") (pin "19") (pinfunction "2~{OE}_19") (pintype "bidirectional"))
    )
    (net (code "27") (name "Net-(IC1-Y3)") (class "Default")
      (node (ref "IC1") (pin "12") (pinfunction "Y3_12") (pintype "bidirectional"))
      (node (ref "IC5") (pin "1") (pinfunction "1~{OE}_1") (pintype "bidirectional"))
      (node (ref "IC5") (pin "19") (pinfunction "2~{OE}_19") (pintype "bidirectional"))
    )
    (net (code "28") (name "Net-(IC1-Y4)") (class "Default")
      (node (ref "IC1") (pin "11") (pinfunction "Y4_11") (pintype "bidirectional"))
      (node (ref "IC8") (pin "1") (pinfunction "1~{OE}_1") (pintype "bidirectional"))
      (node (ref "IC8") (pin "19") (pinfunction "2~{OE}_19") (pintype "bidirectional"))
    )
    (net (code "29") (name "Net-(IC1-Y5)") (class "Default")
      (node (ref "IC1") (pin "10") (pinfunction "Y5_10") (pintype "bidirectional"))
      (node (ref "IC4") (pin "1") (pinfunction "1~{OE}_1") (pintype "bidirectional"))
      (node (ref "IC4") (pin "19") (pinfunction "2~{OE}_19") (pintype "bidirectional"))
    )
    (net (code "30") (name "Net-(IC1-Y6)") (class "Default")
      (node (ref "IC1") (pin "9") (pinfunction "Y6_9") (pintype "bidirectional"))
      (node (ref "IC7") (pin "1") (pinfunction "1~{OE}_1") (pintype "bidirectional"))
      (node (ref "IC7") (pin "19") (pinfunction "2~{OE}_19") (pintype "bidirectional"))
    )
    (net (code "31") (name "Net-(IC1-Y7)") (class "Default")
      (node (ref "IC1") (pin "7") (pinfunction "Y7_7") (pintype "bidirectional"))
      (node (ref "IC3") (pin "1") (pinfunction "1~{OE}_1") (pintype "bidirectional"))
      (node (ref "IC3") (pin "19") (pinfunction "2~{OE}_19") (pintype "bidirectional"))
    )
    (net (code "32") (name "Net-(IC3-1Y1)") (class "Default")
      (node (ref "IC3") (pin "18") (pinfunction "1Y1_18") (pintype "bidirectional"))
      (node (ref "JP40") (pin "1") (pinfunction "1_1") (pintype "passive"))
    )
    (net (code "33") (name "Net-(IC3-1Y2)") (class "Default")
      (node (ref "IC3") (pin "16") (pinfunction "1Y2_16") (pintype "bidirectional"))
      (node (ref "JP42") (pin "1") (pinfunction "1_1") (pintype "passive"))
    )
    (net (code "34") (name "Net-(IC3-1Y3)") (class "Default")
      (node (ref "IC3") (pin "14") (pinfunction "1Y3_14") (pintype "bidirectional"))
      (node (ref "JP44") (pin "1") (pinfunction "1_1") (pintype "passive"))
    )
    (net (code "35") (name "Net-(IC3-1Y4)") (class "Default")
      (node (ref "IC3") (pin "12") (pinfunction "1Y4_12") (pintype "bidirectional"))
      (node (ref "JP48") (pin "1") (pinfunction "1_1") (pintype "passive"))
    )
    (net (code "36") (name "Net-(IC3-2Y1)") (class "Default")
      (node (ref "IC3") (pin "9") (pinfunction "2Y1_9") (pintype "bidirectional"))
      (node (ref "JP58") (pin "1") (pinfunction "1_1") (pintype "passive"))
    )
    (net (code "37") (name "Net-(IC3-2Y2)") (class "Default")
      (node (ref "IC3") (pin "7") (pinfunction "2Y2_7") (pintype "bidirectional"))
      (node (ref "JP54") (pin "1") (pinfunction "1_1") (pintype "passive"))
    )
    (net (code "38") (name "Net-(IC3-2Y3)") (class "Default")
      (node (ref "IC3") (pin "5") (pinfunction "2Y3_5") (pintype "bidirectional"))
      (node (ref "JP52") (pin "1") (pinfunction "1_1") (pintype "passive"))
    )
    (net (code "39") (name "Net-(IC3-2Y4)") (class "Default")
      (node (ref "IC3") (pin "3") (pinfunction "2Y4_3") (pintype "bidirectional"))
      (node (ref "JP50") (pin "1") (pinfunction "1_1") (pintype "passive"))
    )
    (net (code "40") (name "Net-(IC4-1Y1)") (class "Default")
      (node (ref "IC4") (pin "18") (pinfunction "1Y1_18") (pintype "bidirectional"))
      (node (ref "JP22") (pin "1") (pinfunction "1_1") (pintype "passive"))
    )
    (net (code "41") (name "Net-(IC4-1Y2)") (class "Default")
      (node (ref "IC4") (pin "16") (pinfunction "1Y2_16") (pintype "bidirectional"))
      (node (ref "JP24") (pin "1") (pinfunction "1_1") (pintype "passive"))
    )
    (net (code "42") (name "Net-(IC4-1Y3)") (class "Default")
      (node (ref "IC4") (pin "14") (pinfunction "1Y3_14") (pintype "bidirectional"))
      (node (ref "JP26") (pin "1") (pinfunction "1_1") (pintype "passive"))
    )
    (net (code "43") (name "Net-(IC4-1Y4)") (class "Default")
      (node (ref "IC4") (pin "12") (pinfunction "1Y4_12") (pintype "bidirectional"))
      (node (ref "JP28") (pin "1") (pinfunction "1_1") (pintype "passive"))
    )
    (net (code "44") (name "Net-(IC4-2Y1)") (class "Default")
      (node (ref "IC4") (pin "9") (pinfunction "2Y1_9") (pintype "bidirectional"))
      (node (ref "JP36") (pin "1") (pinfunction "1_1") (pintype "passive"))
    )
    (net (code "45") (name "Net-(IC4-2Y2)") (class "Default")
      (node (ref "IC4") (pin "7") (pinfunction "2Y2_7") (pintype "bidirectional"))
      (node (ref "JP34") (pin "1") (pinfunction "1_1") (pintype "passive"))
    )
    (net (code "46") (name "Net-(IC4-2Y3)") (class "Default")
      (node (ref "IC4") (pin "5") (pinfunction "2Y3_5") (pintype "bidirectional"))
      (node (ref "JP32") (pin "1") (pinfunction "1_1") (pintype "passive"))
    )
    (net (code "47") (name "Net-(IC4-2Y4)") (class "Default")
      (node (ref "IC4") (pin "3") (pinfunction "2Y4_3") (pintype "bidirectional"))
      (node (ref "JP30") (pin "1") (pinfunction "1_1") (pintype "passive"))
    )
    (net (code "48") (name "Net-(IC5-1Y1)") (class "Default")
      (node (ref "IC5") (pin "18") (pinfunction "1Y1_18") (pintype "bidirectional"))
      (node (ref "JP4") (pin "1") (pinfunction "1_1") (pintype "passive"))
    )
    (net (code "49") (name "Net-(IC5-1Y2)") (class "Default")
      (node (ref "IC5") (pin "16") (pinfunction "1Y2_16") (pintype "bidirectional"))
      (node (ref "JP6") (pin "1") (pinfunction "1_1") (pintype "passive"))
    )
    (net (code "50") (name "Net-(IC5-1Y3)") (class "Default")
      (node (ref "IC5") (pin "14") (pinfunction "1Y3_14") (pintype "bidirectional"))
      (node (ref "JP8") (pin "1") (pinfunction "1_1") (pintype "passive"))
    )
    (net (code "51") (name "Net-(IC5-1Y4)") (class "Default")
      (node (ref "IC5") (pin "12") (pinfunction "1Y4_12") (pintype "bidirectional"))
      (node (ref "JP10") (pin "1") (pinfunction "1_1") (pintype "passive"))
    )
    (net (code "52") (name "Net-(IC5-2Y1)") (class "Default")
      (node (ref "IC5") (pin "9") (pinfunction "2Y1_9") (pintype "bidirectional"))
      (node (ref "JP18") (pin "1") (pinfunction "1_1") (pintype "passive"))
    )
    (net (code "53") (name "Net-(IC5-2Y2)") (class "Default")
      (node (ref "IC5") (pin "7") (pinfunction "2Y2_7") (pintype "bidirectional"))
      (node (ref "JP16") (pin "1") (pinfunction "1_1") (pintype "passive"))
    )
    (net (code "54") (name "Net-(IC5-2Y3)") (class "Default")
      (node (ref "IC5") (pin "5") (pinfunction "2Y3_5") (pintype "bidirectional"))
      (node (ref "JP14") (pin "1") (pinfunction "1_1") (pintype "passive"))
    )
    (net (code "55") (name "Net-(IC5-2Y4)") (class "Default")
      (node (ref "IC5") (pin "3") (pinfunction "2Y4_3") (pintype "bidirectional"))
      (node (ref "JP12") (pin "1") (pinfunction "1_1") (pintype "passive"))
    )
    (net (code "56") (name "Net-(IC6-1Y1)") (class "Default")
      (node (ref "IC6") (pin "18") (pinfunction "1Y1_18") (pintype "bidirectional"))
      (node (ref "JP1") (pin "1") (pinfunction "1_1") (pintype "passive"))
    )
    (net (code "57") (name "Net-(IC6-1Y2)") (class "Default")
      (node (ref "IC6") (pin "16") (pinfunction "1Y2_16") (pintype "bidirectional"))
      (node (ref "JP19") (pin "1") (pinfunction "1_1") (pintype "passive"))
    )
    (net (code "58") (name "Net-(IC6-1Y3)") (class "Default")
      (node (ref "IC6") (pin "14") (pinfunction "1Y3_14") (pintype "bidirectional"))
      (node (ref "JP37") (pin "1") (pinfunction "1_1") (pintype "passive"))
    )
    (net (code "59") (name "Net-(IC6-1Y4)") (class "Default")
      (node (ref "IC6") (pin "12") (pinfunction "1Y4_12") (pintype "bidirectional"))
      (node (ref "JP46") (pin "1") (pinfunction "1_1") (pintype "passive"))
    )
    (net (code "60") (name "Net-(IC6-2Y1)") (class "Default")
      (node (ref "IC6") (pin "9") (pinfunction "2Y1_9") (pintype "bidirectional"))
      (node (ref "JP55") (pin "1") (pinfunction "1_1") (pintype "passive"))
    )
    (net (code "61") (name "Net-(IC6-2Y2)") (class "Default")
      (node (ref "IC6") (pin "7") (pinfunction "2Y2_7") (pintype "bidirectional"))
      (node (ref "JP64") (pin "1") (pinfunction "1_1") (pintype "passive"))
    )
    (net (code "62") (name "Net-(IC6-2Y3)") (class "Default")
      (node (ref "IC6") (pin "5") (pinfunction "2Y3_5") (pintype "bidirectional"))
      (node (ref "JP73") (pin "1") (pinfunction "1_1") (pintype "passive"))
    )
    (net (code "63") (name "Net-(IC6-2Y4)") (class "Default")
      (node (ref "IC6") (pin "3") (pinfunction "2Y4_3") (pintype "bidirectional"))
      (node (ref "JP82") (pin "1") (pinfunction "1_1") (pintype "passive"))
    )
    (net (code "64") (name "Net-(IC7-1Y1)") (class "Default")
      (node (ref "IC7") (pin "18") (pinfunction "1Y1_18") (pintype "bidirectional"))
      (node (ref "JP39") (pin "1") (pinfunction "1_1") (pintype "passive"))
    )
    (net (code "65") (name "Net-(IC7-1Y2)") (class "Default")
      (node (ref "IC7") (pin "16") (pinfunction "1Y2_16") (pintype "bidirectional"))
      (node (ref "JP41") (pin "1") (pinfunction "1_1") (pintype "passive"))
    )
    (net (code "66") (name "Net-(IC7-1Y3)") (class "Default")
      (node (ref "IC7") (pin "14") (pinfunction "1Y3_14") (pintype "bidirectional"))
      (node (ref "JP43") (pin "1") (pinfunction "1_1") (pintype "passive"))
    )
    (net (code "67") (name "Net-(IC7-1Y4)") (class "Default")
      (node (ref "IC7") (pin "12") (pinfunction "1Y4_12") (pintype "bidirectional"))
      (node (ref "JP45") (pin "1") (pinfunction "1_1") (pintype "passive"))
    )
    (net (code "68") (name "Net-(IC7-2Y1)") (class "Default")
      (node (ref "IC7") (pin "9") (pinfunction "2Y1_9") (pintype "bidirectional"))
      (node (ref "JP49") (pin "1") (pinfunction "1_1") (pintype "passive"))
    )
    (net (code "69") (name "Net-(IC7-2Y2)") (class "Default")
      (node (ref "IC7") (pin "7") (pinfunction "2Y2_7") (pintype "bidirectional"))
      (node (ref "JP51") (pin "1") (pinfunction "1_1") (pintype "passive"))
    )
    (net (code "70") (name "Net-(IC7-2Y3)") (class "Default")
      (node (ref "IC7") (pin "5") (pinfunction "2Y3_5") (pintype "bidirectional"))
      (node (ref "JP53") (pin "1") (pinfunction "1_1") (pintype "passive"))
    )
    (net (code "71") (name "Net-(IC7-2Y4)") (class "Default")
      (node (ref "IC7") (pin "3") (pinfunction "2Y4_3") (pintype "bidirectional"))
      (node (ref "JP57") (pin "1") (pinfunction "1_1") (pintype "passive"))
    )
    (net (code "72") (name "Net-(IC8-1Y1)") (class "Default")
      (node (ref "IC8") (pin "18") (pinfunction "1Y1_18") (pintype "bidirectional"))
      (node (ref "JP21") (pin "1") (pinfunction "1_1") (pintype "passive"))
    )
    (net (code "73") (name "Net-(IC8-1Y2)") (class "Default")
      (node (ref "IC8") (pin "16") (pinfunction "1Y2_16") (pintype "bidirectional"))
      (node (ref "JP23") (pin "1") (pinfunction "1_1") (pintype "passive"))
    )
    (net (code "74") (name "Net-(IC8-1Y3)") (class "Default")
      (node (ref "IC8") (pin "14") (pinfunction "1Y3_14") (pintype "bidirectional"))
      (node (ref "JP25") (pin "1") (pinfunction "1_1") (pintype "passive"))
    )
    (net (code "75") (name "Net-(IC8-1Y4)") (class "Default")
      (node (ref "IC8") (pin "12") (pinfunction "1Y4_12") (pintype "bidirectional"))
      (node (ref "JP27") (pin "1") (pinfunction "1_1") (pintype "passive"))
    )
    (net (code "76") (name "Net-(IC8-2Y1)") (class "Default")
      (node (ref "IC8") (pin "9") (pinfunction "2Y1_9") (pintype "bidirectional"))
      (node (ref "JP29") (pin "1") (pinfunction "1_1") (pintype "passive"))
    )
    (net (code "77") (name "Net-(IC8-2Y2)") (class "Default")
      (node (ref "IC8") (pin "7") (pinfunction "2Y2_7") (pintype "bidirectional"))
      (node (ref "JP31") (pin "1") (pinfunction "1_1") (pintype "passive"))
    )
    (net (code "78") (name "Net-(IC8-2Y3)") (class "Default")
      (node (ref "IC8") (pin "5") (pinfunction "2Y3_5") (pintype "bidirectional"))
      (node (ref "JP33") (pin "1") (pinfunction "1_1") (pintype "passive"))
    )
    (net (code "79") (name "Net-(IC8-2Y4)") (class "Default")
      (node (ref "IC8") (pin "3") (pinfunction "2Y4_3") (pintype "bidirectional"))
      (node (ref "JP35") (pin "1") (pinfunction "1_1") (pintype "passive"))
    )
    (net (code "80") (name "Net-(IC9-1Y1)") (class "Default")
      (node (ref "IC9") (pin "18") (pinfunction "1Y1_18") (pintype "bidirectional"))
      (node (ref "JP3") (pin "1") (pinfunction "1_1") (pintype "passive"))
    )
    (net (code "81") (name "Net-(IC9-1Y2)") (class "Default")
      (node (ref "IC9") (pin "16") (pinfunction "1Y2_16") (pintype "bidirectional"))
      (node (ref "JP5") (pin "1") (pinfunction "1_1") (pintype "passive"))
    )
    (net (code "82") (name "Net-(IC9-1Y3)") (class "Default")
      (node (ref "IC9") (pin "14") (pinfunction "1Y3_14") (pintype "bidirectional"))
      (node (ref "JP7") (pin "1") (pinfunction "1_1") (pintype "passive"))
    )
    (net (code "83") (name "Net-(IC9-1Y4)") (class "Default")
      (node (ref "IC9") (pin "12") (pinfunction "1Y4_12") (pintype "bidirectional"))
      (node (ref "JP9") (pin "1") (pinfunction "1_1") (pintype "passive"))
    )
    (net (code "84") (name "Net-(IC9-2Y1)") (class "Default")
      (node (ref "IC9") (pin "9") (pinfunction "2Y1_9") (pintype "bidirectional"))
      (node (ref "JP11") (pin "1") (pinfunction "1_1") (pintype "passive"))
    )
    (net (code "85") (name "Net-(IC9-2Y2)") (class "Default")
      (node (ref "IC9") (pin "7") (pinfunction "2Y2_7") (pintype "bidirectional"))
      (node (ref "JP13") (pin "1") (pinfunction "1_1") (pintype "passive"))
    )
    (net (code "86") (name "Net-(IC9-2Y3)") (class "Default")
      (node (ref "IC9") (pin "5") (pinfunction "2Y3_5") (pintype "bidirectional"))
      (node (ref "JP15") (pin "1") (pinfunction "1_1") (pintype "passive"))
    )
    (net (code "87") (name "Net-(IC9-2Y4)") (class "Default")
      (node (ref "IC9") (pin "3") (pinfunction "2Y4_3") (pintype "bidirectional"))
      (node (ref "JP17") (pin "1") (pinfunction "1_1") (pintype "passive"))
    )
    (net (code "88") (name "Net-(IC10-1Y1)") (class "Default")
      (node (ref "IC10") (pin "18") (pinfunction "1Y1_18") (pintype "bidirectional"))
      (node (ref "JP2") (pin "1") (pinfunction "1_1") (pintype "passive"))
    )
    (net (code "89") (name "Net-(IC10-1Y2)") (class "Default")
      (node (ref "IC10") (pin "16") (pinfunction "1Y2_16") (pintype "bidirectional"))
      (node (ref "JP20") (pin "1") (pinfunction "1_1") (pintype "passive"))
    )
    (net (code "90") (name "Net-(IC10-1Y3)") (class "Default")
      (node (ref "IC10") (pin "14") (pinfunction "1Y3_14") (pintype "bidirectional"))
      (node (ref "JP38") (pin "1") (pinfunction "1_1") (pintype "passive"))
    )
    (net (code "91") (name "Net-(IC10-1Y4)") (class "Default")
      (node (ref "IC10") (pin "12") (pinfunction "1Y4_12") (pintype "bidirectional"))
      (node (ref "JP47") (pin "1") (pinfunction "1_1") (pintype "passive"))
    )
    (net (code "92") (name "Net-(IC10-2Y1)") (class "Default")
      (node (ref "IC10") (pin "9") (pinfunction "2Y1_9") (pintype "bidirectional"))
      (node (ref "JP83") (pin "1") (pinfunction "1_1") (pintype "passive"))
    )
    (net (code "93") (name "Net-(IC10-2Y2)") (class "Default")
      (node (ref "IC10") (pin "7") (pinfunction "2Y2_7") (pintype "bidirectional"))
      (node (ref "JP74") (pin "1") (pinfunction "1_1") (pintype "passive"))
    )
    (net (code "94") (name "Net-(IC10-2Y3)") (class "Default")
      (node (ref "IC10") (pin "5") (pinfunction "2Y3_5") (pintype "bidirectional"))
      (node (ref "JP65") (pin "1") (pinfunction "1_1") (pintype "passive"))
    )
    (net (code "95") (name "Net-(IC10-2Y4)") (class "Default")
      (node (ref "IC10") (pin "3") (pinfunction "2Y4_3") (pintype "bidirectional"))
      (node (ref "JP56") (pin "1") (pinfunction "1_1") (pintype "passive"))
    )
    (net (code "96") (name "Net-(IC11-2Y)") (class "Default")
      (node (ref "IC11") (pin "4") (pinfunction "2Y_4") (pintype "bidirectional"))
      (node (ref "J1") (pin "5") (pinfunction "CLK_5") (pintype "bidirectional"))
    )
    (net (code "97") (name "Net-(IC11-3Y)") (class "Default")
      (node (ref "IC11") (pin "6") (pinfunction "3Y_6") (pintype "bidirectional"))
      (node (ref "J1") (pin "3") (pinfunction "CMD_3") (pintype "bidirectional"))
    )
    (net (code "98") (name "Net-(IC11-4Y)") (class "Default")
      (node (ref "IC11") (pin "10") (pinfunction "4Y_10") (pintype "bidirectional"))
      (node (ref "J1") (pin "2") (pinfunction "CD/DAT3_2") (pintype "bidirectional"))
    )
    (net (code "99") (name "Net-(IC13-(PCINT14{slash}RESET)_PC6)") (class "Default")
      (node (ref "IC13") (pin "1") (pinfunction "(PCINT14/RESET)_PC6_1") (pintype "bidirectional"))
      (node (ref "R9") (pin "2") (pinfunction "2_2") (pintype "passive"))
    )
    (net (code "100") (name "Net-(IC13-PC0_(ADC0{slash}PCINT8))") (class "Default")
      (node (ref "B_RIGHT") (pin "2") (pinfunction "2_2") (pintype "bidirectional"))
      (node (ref "IC13") (pin "23") (pinfunction "PC0_(ADC0/PCINT8)_23") (pintype "bidirectional"))
      (node (ref "R10") (pin "1") (pinfunction "1_1") (pintype "passive"))
    )
    (net (code "101") (name "Net-(Q9-D)") (class "Default")
      (node (ref "Q9") (pin "2") (pinfunction "D_2") (pintype "bidirectional"))
      (node (ref "R4") (pin "2") (pinfunction "2_2") (pintype "passive"))
    )
    (net (code "102") (name "Net-(Q9-S)") (class "Default")
      (node (ref "L_1_2") (pin "1") (pinfunction "1_1") (pintype "bidirectional"))
      (node (ref "Q9") (pin "3") (pinfunction "S_3") (pintype "bidirectional"))
    )
    (net (code "103") (name "Net-(Q10-D)") (class "Default")
      (node (ref "Q10") (pin "2") (pinfunction "D_2") (pintype "bidirectional"))
      (node (ref "R5") (pin "2") (pinfunction "2_2") (pintype "passive"))
    )
    (net (code "104") (name "Net-(Q10-S)") (class "Default")
      (node (ref "L_7_8") (pin "2") (pinfunction "2_2") (pintype "bidirectional"))
      (node (ref "Q10") (pin "3") (pinfunction "S_3") (pintype "bidirectional"))
    )
    (net (code "105") (name "Net-(Q11-D)") (class "Default")
      (node (ref "Q11") (pin "2") (pinfunction "D_2") (pintype "bidirectional"))
      (node (ref "R3") (pin "2") (pinfunction "2_2") (pintype "passive"))
    )
    (net (code "106") (name "Net-(Q11-S)") (class "Default")
      (node (ref "L_1_2") (pin "2") (pinfunction "2_2") (pintype "bidirectional"))
      (node (ref "Q11") (pin "3") (pinfunction "S_3") (pintype "bidirectional"))
    )
    (net (code "107") (name "Net-(Q12-D)") (class "Default")
      (node (ref "Q12") (pin "2") (pinfunction "D_2") (pintype "bidirectional"))
      (node (ref "R8") (pin "2") (pinfunction "2_2") (pintype "passive"))
    )
    (net (code "108") (name "Net-(Q12-S)") (class "Default")
      (node (ref "L_3_4") (pin "1") (pinfunction "1_1") (pintype "bidirectional"))
      (node (ref "Q12") (pin "3") (pinfunction "S_3") (pintype "bidirectional"))
    )
    (net (code "109") (name "Net-(Q13-D)") (class "Default")
      (node (ref "Q13") (pin "2") (pinfunction "D_2") (pintype "bidirectional"))
      (node (ref "R6") (pin "2") (pinfunction "2_2") (pintype "passive"))
    )
    (net (code "110") (name "Net-(Q13-S)") (class "Default")
      (node (ref "L_7_8") (pin "1") (pinfunction "1_1") (pintype "bidirectional"))
      (node (ref "Q13") (pin "3") (pinfunction "S_3") (pintype "bidirectional"))
    )
    (net (code "111") (name "Net-(Q14-D)") (class "Default")
      (node (ref "Q14") (pin "2") (pinfunction "D_2") (pintype "bidirectional"))
      (node (ref "R1") (pin "2") (pinfunction "2_2") (pintype "passive"))
    )
    (net (code "112") (name "Net-(Q14-S)") (class "Default")
      (node (ref "L_5_6") (pin "2") (pinfunction "2_2") (pintype "bidirectional"))
      (node (ref "Q14") (pin "3") (pinfunction "S_3") (pintype "bidirectional"))
    )
    (net (code "113") (name "Net-(Q15-D)") (class "Default")
      (node (ref "Q15") (pin "2") (pinfunction "D_2") (pintype "bidirectional"))
      (node (ref "R2") (pin "2") (pinfunction "2_2") (pintype "passive"))
    )
    (net (code "114") (name "Net-(Q15-S)") (class "Default")
      (node (ref "L_5_6") (pin "1") (pinfunction "1_1") (pintype "bidirectional"))
      (node (ref "Q15") (pin "3") (pinfunction "S_3") (pintype "bidirectional"))
    )
    (net (code "115") (name "Net-(Q16-D)") (class "Default")
      (node (ref "Q16") (pin "2") (pinfunction "D_2") (pintype "bidirectional"))
      (node (ref "R7") (pin "2") (pinfunction "2_2") (pintype "passive"))
    )
    (net (code "116") (name "Net-(Q16-S)") (class "Default")
      (node (ref "L_3_4") (pin "2") (pinfunction "2_2") (pintype "bidirectional"))
      (node (ref "Q16") (pin "3") (pinfunction "S_3") (pintype "bidirectional"))
    )
    (net (code "117") (name "Y1") (class "Default")
      (node (ref "IC10") (pin "2") (pinfunction "1A1_2") (pintype "bidirectional"))
      (node (ref "IC2") (pin "15") (pinfunction "Y0_15") (pintype "bidirectional"))
      (node (ref "IC3") (pin "2") (pinfunction "1A1_2") (pintype "bidirectional"))
      (node (ref "IC4") (pin "2") (pinfunction "1A1_2") (pintype "bidirectional"))
      (node (ref "IC5") (pin "2") (pinfunction "1A1_2") (pintype "bidirectional"))
      (node (ref "IC6") (pin "2") (pinfunction "1A1_2") (pintype "bidirectional"))
      (node (ref "IC7") (pin "2") (pinfunction "1A1_2") (pintype "bidirectional"))
      (node (ref "IC8") (pin "2") (pinfunction "1A1_2") (pintype "bidirectional"))
      (node (ref "IC9") (pin "2") (pinfunction "1A1_2") (pintype "bidirectional"))
    )
    (net (code "118") (name "Y2") (class "Default")
      (node (ref "IC10") (pin "4") (pinfunction "1A2_4") (pintype "bidirectional"))
      (node (ref "IC2") (pin "14") (pinfunction "Y1_14") (pintype "bidirectional"))
      (node (ref "IC3") (pin "4") (pinfunction "1A2_4") (pintype "bidirectional"))
      (node (ref "IC4") (pin "4") (pinfunction "1A2_4") (pintype "bidirectional"))
      (node (ref "IC5") (pin "4") (pinfunction "1A2_4") (pintype "bidirectional"))
      (node (ref "IC6") (pin "4") (pinfunction "1A2_4") (pintype "bidirectional"))
      (node (ref "IC7") (pin "4") (pinfunction "1A2_4") (pintype "bidirectional"))
      (node (ref "IC8") (pin "4") (pinfunction "1A2_4") (pintype "bidirectional"))
      (node (ref "IC9") (pin "4") (pinfunction "1A2_4") (pintype "bidirectional"))
    )
    (net (code "119") (name "Y3") (class "Default")
      (node (ref "IC10") (pin "6") (pinfunction "1A3_6") (pintype "bidirectional"))
      (node (ref "IC2") (pin "13") (pinfunction "Y2_13") (pintype "bidirectional"))
      (node (ref "IC3") (pin "6") (pinfunction "1A3_6") (pintype "bidirectional"))
      (node (ref "IC4") (pin "6") (pinfunction "1A3_6") (pintype "bidirectional"))
      (node (ref "IC5") (pin "6") (pinfunction "1A3_6") (pintype "bidirectional"))
      (node (ref "IC6") (pin "6") (pinfunction "1A3_6") (pintype "bidirectional"))
      (node (ref "IC7") (pin "6") (pinfunction "1A3_6") (pintype "bidirectional"))
      (node (ref "IC8") (pin "6") (pinfunction "1A3_6") (pintype "bidirectional"))
      (node (ref "IC9") (pin "6") (pinfunction "1A3_6") (pintype "bidirectional"))
    )
    (net (code "120") (name "Y4") (class "Default")
      (node (ref "IC10") (pin "8") (pinfunction "1A4_8") (pintype "bidirectional"))
      (node (ref "IC2") (pin "12") (pinfunction "Y3_12") (pintype "bidirectional"))
      (node (ref "IC3") (pin "8") (pinfunction "1A4_8") (pintype "bidirectional"))
      (node (ref "IC4") (pin "8") (pinfunction "1A4_8") (pintype "bidirectional"))
      (node (ref "IC5") (pin "8") (pinfunction "1A4_8") (pintype "bidirectional"))
      (node (ref "IC6") (pin "8") (pinfunction "1A4_8") (pintype "bidirectional"))
      (node (ref "IC7") (pin "8") (pinfunction "1A4_8") (pintype "bidirectional"))
      (node (ref "IC8") (pin "8") (pinfunction "1A4_8") (pintype "bidirectional"))
      (node (ref "IC9") (pin "8") (pinfunction "1A4_8") (pintype "bidirectional"))
    )
    (net (code "121") (name "Y5") (class "Default")
      (node (ref "IC10") (pin "17") (pinfunction "2A4_17") (pintype "bidirectional"))
      (node (ref "IC2") (pin "11") (pinfunction "Y4_11") (pintype "bidirectional"))
      (node (ref "IC3") (pin "17") (pinfunction "2A4_17") (pintype "bidirectional"))
      (node (ref "IC4") (pin "17") (pinfunction "2A4_17") (pintype "bidirectional"))
      (node (ref "IC5") (pin "17") (pinfunction "2A4_17") (pintype "bidirectional"))
      (node (ref "IC6") (pin "11") (pinfunction "2A1_11") (pintype "bidirectional"))
      (node (ref "IC7") (pin "11") (pinfunction "2A1_11") (pintype "bidirectional"))
      (node (ref "IC8") (pin "11") (pinfunction "2A1_11") (pintype "bidirectional"))
      (node (ref "IC9") (pin "11") (pinfunction "2A1_11") (pintype "bidirectional"))
    )
    (net (code "122") (name "Y6") (class "Default")
      (node (ref "IC10") (pin "15") (pinfunction "2A3_15") (pintype "bidirectional"))
      (node (ref "IC2") (pin "10") (pinfunction "Y5_10") (pintype "bidirectional"))
      (node (ref "IC3") (pin "15") (pinfunction "2A3_15") (pintype "bidirectional"))
      (node (ref "IC4") (pin "15") (pinfunction "2A3_15") (pintype "bidirectional"))
      (node (ref "IC5") (pin "15") (pinfunction "2A3_15") (pintype "bidirectional"))
      (node (ref "IC6") (pin "13") (pinfunction "2A2_13") (pintype "bidirectional"))
      (node (ref "IC7") (pin "13") (pinfunction "2A2_13") (pintype "bidirectional"))
      (node (ref "IC8") (pin "13") (pinfunction "2A2_13") (pintype "bidirectional"))
      (node (ref "IC9") (pin "13") (pinfunction "2A2_13") (pintype "bidirectional"))
    )
    (net (code "123") (name "Y7") (class "Default")
      (node (ref "IC10") (pin "13") (pinfunction "2A2_13") (pintype "bidirectional"))
      (node (ref "IC2") (pin "9") (pinfunction "Y6_9") (pintype "bidirectional"))
      (node (ref "IC3") (pin "13") (pinfunction "2A2_13") (pintype "bidirectional"))
      (node (ref "IC4") (pin "13") (pinfunction "2A2_13") (pintype "bidirectional"))
      (node (ref "IC5") (pin "13") (pinfunction "2A2_13") (pintype "bidirectional"))
      (node (ref "IC6") (pin "15") (pinfunction "2A3_15") (pintype "bidirectional"))
      (node (ref "IC7") (pin "15") (pinfunction "2A3_15") (pintype "bidirectional"))
      (node (ref "IC8") (pin "15") (pinfunction "2A3_15") (pintype "bidirectional"))
      (node (ref "IC9") (pin "15") (pinfunction "2A3_15") (pintype "bidirectional"))
    )
    (net (code "124") (name "Y8") (class "Default")
      (node (ref "IC10") (pin "11") (pinfunction "2A1_11") (pintype "bidirectional"))
      (node (ref "IC2") (pin "7") (pinfunction "Y7_7") (pintype "bidirectional"))
      (node (ref "IC3") (pin "11") (pinfunction "2A1_11") (pintype "bidirectional"))
      (node (ref "IC4") (pin "11") (pinfunction "2A1_11") (pintype "bidirectional"))
      (node (ref "IC5") (pin "11") (pinfunction "2A1_11") (pintype "bidirectional"))
      (node (ref "IC6") (pin "17") (pinfunction "2A4_17") (pintype "bidirectional"))
      (node (ref "IC7") (pin "17") (pinfunction "2A4_17") (pintype "bidirectional"))
      (node (ref "IC8") (pin "17") (pinfunction "2A4_17") (pintype "bidirectional"))
      (node (ref "IC9") (pin "17") (pinfunction "2A4_17") (pintype "bidirectional"))
    )
    (net (code "125") (name "Z0") (class "Default")
      (node (ref "IC12") (pin "3") (pinfunction "C_3") (pintype "input"))
      (node (ref "IC13") (pin "14") (pinfunction "(PCINT0/CLKO/ICP1)_PB0_14") (pintype "bidirectional"))
      (node (ref "U$2") (pin "D8") (pinfunction "D8_D8") (pintype "bidirectional"))
    )
    (net (code "126") (name "Z1") (class "Default")
      (node (ref "IC12") (pin "2") (pinfunction "B_2") (pintype "input"))
      (node (ref "IC13") (pin "13") (pinfunction "(PCINT23/AIN1)_PD7_13") (pintype "bidirectional"))
      (node (ref "U$2") (pin "D7") (pinfunction "D7_D7") (pintype "bidirectional"))
    )
    (net (code "127") (name "Z2") (class "Default")
      (node (ref "IC12") (pin "1") (pinfunction "A_1") (pintype "input"))
      (node (ref "IC13") (pin "12") (pinfunction "(PCINT22/OC0A/AIN0)_PD6_12") (pintype "bidirectional"))
      (node (ref "U$2") (pin "D6") (pinfunction "D6_D6") (pintype "bidirectional"))
    )
    (net (code "128") (name "unconnected-(IC11-1Y-Pad2)") (class "Default")
      (node (ref "IC11") (pin "2") (pinfunction "1Y_2") (pintype "bidirectional"))
    )
    (net (code "129") (name "unconnected-(IC11-5Y-Pad12)") (class "Default")
      (node (ref "IC11") (pin "12") (pinfunction "5Y_12") (pintype "bidirectional"))
    )
    (net (code "130") (name "unconnected-(IC11-6Y-Pad15)") (class "Default")
      (node (ref "IC11") (pin "15") (pinfunction "6Y_15") (pintype "bidirectional"))
    )
    (net (code "131") (name "unconnected-(IC11-NC-Pad16)") (class "Default")
      (node (ref "IC11") (pin "16") (pinfunction "NC_16") (pintype "no_connect"))
    )
    (net (code "132") (name "unconnected-(IC11-NC_2-Pad13)") (class "Default")
      (node (ref "IC11") (pin "13") (pinfunction "NC_2_13") (pintype "bidirectional"))
    )
    (net (code "133") (name "unconnected-(IC13-(PCINT6{slash}XTAL1{slash}TOSC1)_PB6-Pad9)") (class "Default")
      (node (ref "IC13") (pin "9") (pinfunction "(PCINT6/XTAL1/TOSC1)_PB6_9") (pintype "bidirectional"))
    )
    (net (code "134") (name "unconnected-(IC13-(PCINT7{slash}XTAL2{slash}TOSC2)_PB7-Pad10)") (class "Default")
      (node (ref "IC13") (pin "10") (pinfunction "(PCINT7/XTAL2/TOSC2)_PB7_10") (pintype "bidirectional"))
    )
    (net (code "135") (name "unconnected-(IC13-AREF-Pad21)") (class "Default")
      (node (ref "IC13") (pin "21") (pinfunction "AREF_21") (pintype "bidirectional"))
    )
    (net (code "136") (name "unconnected-(IC13-PC1_(ADC1{slash}PCINT9)-Pad24)") (class "Default")
      (node (ref "IC13") (pin "24") (pinfunction "PC1_(ADC1/PCINT9)_24") (pintype "bidirectional"))
    )
    (net (code "137") (name "unconnected-(IC13-PC2_(ADC2{slash}PCINT10)-Pad25)") (class "Default")
      (node (ref "IC13") (pin "25") (pinfunction "PC2_(ADC2/PCINT10)_25") (pintype "bidirectional"))
    )
    (net (code "138") (name "unconnected-(IC13-PC3_(ADC3{slash}PCINT11)-Pad26)") (class "Default")
      (node (ref "IC13") (pin "26") (pinfunction "PC3_(ADC3/PCINT11)_26") (pintype "bidirectional"))
    )
    (net (code "139") (name "unconnected-(IC13-PC4_(ADC4{slash}SDA{slash}PCINT12)-Pad27)") (class "Default")
      (node (ref "IC13") (pin "27") (pinfunction "PC4_(ADC4/SDA/PCINT12)_27") (pintype "bidirectional"))
    )
    (net (code "140") (name "unconnected-(IC13-PC5_(ADC5{slash}SCL{slash}PCINT13)-Pad28)") (class "Default")
      (node (ref "IC13") (pin "28") (pinfunction "PC5_(ADC5/SCL/PCINT13)_28") (pintype "bidirectional"))
    )
    (net (code "141") (name "unconnected-(J1-DAT1-Pad8)") (class "Default")
      (node (ref "J1") (pin "8") (pinfunction "DAT1_8") (pintype "bidirectional"))
    )
    (net (code "142") (name "unconnected-(J1-DAT2-Pad1)") (class "Default")
      (node (ref "J1") (pin "1") (pinfunction "DAT2_1") (pintype "bidirectional"))
    )
    (net (code "143") (name "unconnected-(U$1-NC-Pad4)") (class "Default")
      (node (ref "U$1") (pin "4") (pinfunction "NC_4") (pintype "bidirectional"))
    )
    (net (code "144") (name "unconnected-(U$2-PadA0)") (class "Default")
      (node (ref "U$2") (pin "A0") (pinfunction "A0_A0") (pintype "bidirectional"))
    )
    (net (code "145") (name "unconnected-(U$2-PadA1)") (class "Default")
      (node (ref "U$2") (pin "A1") (pinfunction "A1_A1") (pintype "bidirectional"))
    )
    (net (code "146") (name "unconnected-(U$2-PadA2)") (class "Default")
      (node (ref "U$2") (pin "A2") (pinfunction "A2_A2") (pintype "bidirectional"))
    )
    (net (code "147") (name "unconnected-(U$2-PadA3)") (class "Default")
      (node (ref "U$2") (pin "A3") (pinfunction "A3_A3") (pintype "bidirectional"))
    )
    (net (code "148") (name "unconnected-(U$2-PadA4)") (class "Default")
      (node (ref "U$2") (pin "A4") (pinfunction "A4_A4") (pintype "bidirectional"))
    )
    (net (code "149") (name "unconnected-(U$2-PadA5)") (class "Default")
      (node (ref "U$2") (pin "A5") (pinfunction "A5_A5") (pintype "bidirectional"))
    )
    (net (code "150") (name "unconnected-(U$2-PadAREF)") (class "Default")
      (node (ref "U$2") (pin "AREF") (pinfunction "AREF_AREF") (pintype "bidirectional"))
    )
    (net (code "151") (name "unconnected-(U$2-PadD0)") (class "Default")
      (node (ref "U$2") (pin "D0") (pinfunction "D0_D0") (pintype "bidirectional"))
    )
    (net (code "152") (name "unconnected-(U$2-PadD1)") (class "Default")
      (node (ref "U$2") (pin "D1") (pinfunction "D1_D1") (pintype "bidirectional"))
    )
    (net (code "153") (name "unconnected-(U$2-PadD2)") (class "Default")
      (node (ref "U$2") (pin "D2") (pinfunction "D2_D2") (pintype "bidirectional"))
    )
    (net (code "154") (name "unconnected-(U$2-PadD3)") (class "Default")
      (node (ref "U$2") (pin "D3") (pinfunction "D3_D3") (pintype "bidirectional"))
    )
    (net (code "155") (name "unconnected-(U$2-PadD4)") (class "Default")
      (node (ref "U$2") (pin "D4") (pinfunction "D4_D4") (pintype "bidirectional"))
    )
    (net (code "156") (name "unconnected-(U$2-PadD5)") (class "Default")
      (node (ref "U$2") (pin "D5") (pinfunction "D5_D5") (pintype "bidirectional"))
    )
    (net (code "157") (name "unconnected-(U$2-{slash}RESET-PadRESET)") (class "Default")
      (node (ref "U$2") (pin "RESET") (pinfunction "/RESET_RESET") (pintype "bidirectional"))
    )
  )
)
